# RadioPixelHardware.net
KiCad netlist of a schematic drawn in EAGLE
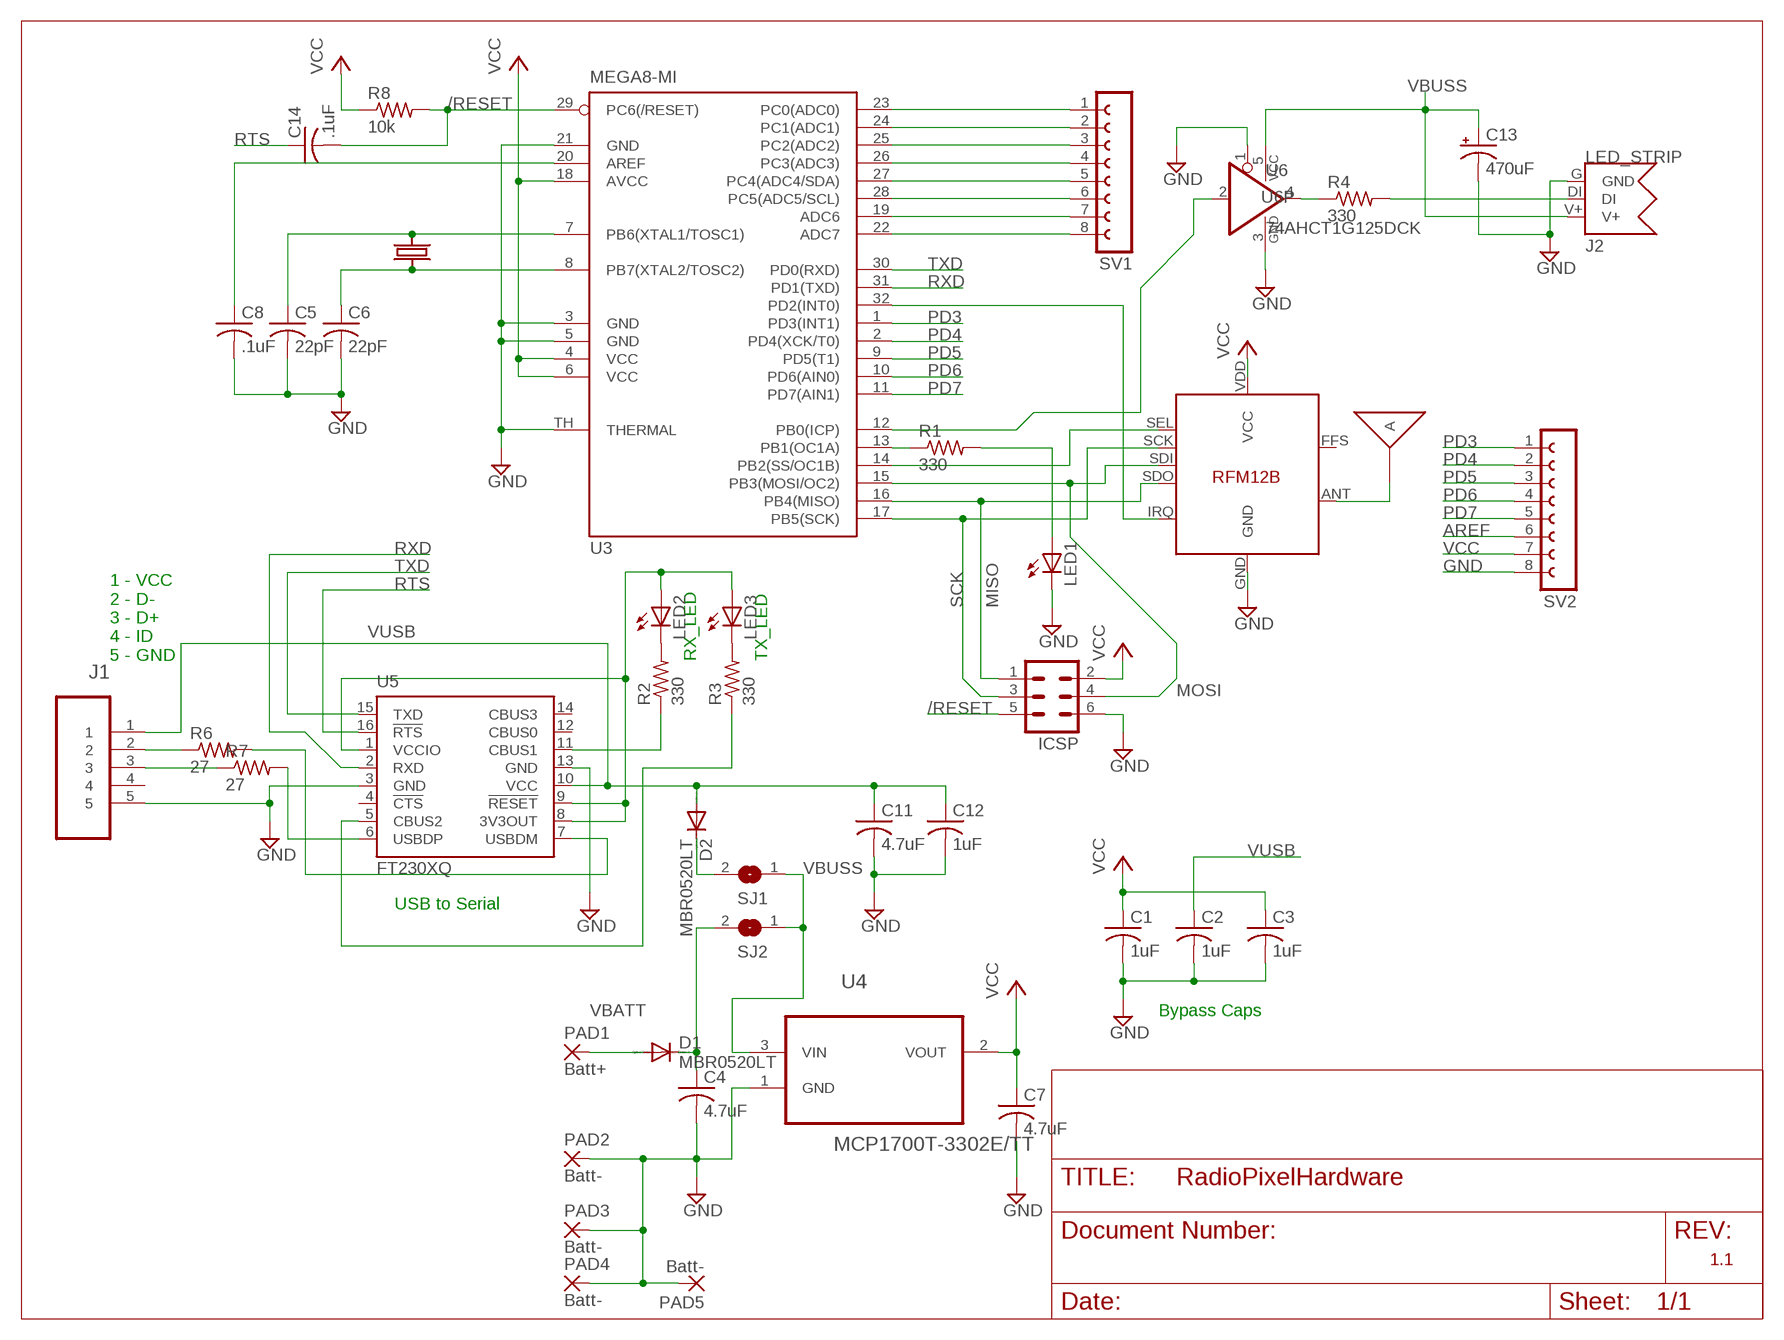
[diagram p0: schematic, sheet 1]

(export (version "E")
  (design (tool "Eeschema 10.0.6"))
  (components
    (comp (ref "C1")
      (value "1uF")
      (footprint "eagle-import:C0603")
      (libsource (lib "eagle-import") (part "C-USC0603"))
    )
    (comp (ref "C2")
      (value "1uF")
      (footprint "eagle-import:C0603")
      (libsource (lib "eagle-import") (part "C-USC0603"))
    )
    (comp (ref "C3")
      (value "1uF")
      (footprint "eagle-import:C0603")
      (libsource (lib "eagle-import") (part "C-USC0603"))
    )
    (comp (ref "C4")
      (value "4.7uF")
      (footprint "eagle-import:C0603")
      (libsource (lib "eagle-import") (part "C-USC0603"))
    )
    (comp (ref "C5")
      (value "22pF")
      (footprint "eagle-import:C0603")
      (libsource (lib "eagle-import") (part "C-USC0603"))
    )
    (comp (ref "C6")
      (value "22pF")
      (footprint "eagle-import:C0603")
      (libsource (lib "eagle-import") (part "C-USC0603"))
    )
    (comp (ref "C7")
      (value "4.7uF")
      (footprint "eagle-import:C0603")
      (libsource (lib "eagle-import") (part "C-USC0603"))
    )
    (comp (ref "C8")
      (value ".1uF")
      (footprint "eagle-import:C0603")
      (libsource (lib "eagle-import") (part "C-USC0603"))
    )
    (comp (ref "C11")
      (value "4.7uF")
      (footprint "eagle-import:C0603")
      (libsource (lib "eagle-import") (part "C-USC0603"))
    )
    (comp (ref "C12")
      (value "1uF")
      (footprint "eagle-import:C0603")
      (libsource (lib "eagle-import") (part "C-USC0603"))
    )
    (comp (ref "C13")
      (value "470uF")
      (footprint "eagle-import:TT2D4L")
      (libsource (lib "eagle-import") (part "CPOL-USTT2D4L"))
    )
    (comp (ref "C14")
      (value ".1uF")
      (footprint "eagle-import:C0603")
      (libsource (lib "eagle-import") (part "C-USC0603"))
    )
    (comp (ref "D1")
      (value "MBR0520LT")
      (footprint "eagle-import:SOD123")
      (libsource (lib "eagle-import") (part "MBR0520LT"))
    )
    (comp (ref "D2")
      (value "MBR0520LT")
      (footprint "eagle-import:SOD123")
      (libsource (lib "eagle-import") (part "MBR0520LT"))
    )
    (comp (ref "ICSP")
      (value "MA03-2")
      (footprint "eagle-import:MA03-2")
      (libsource (lib "eagle-import") (part "MA03-2"))
    )
    (comp (ref "J1")
      (value "47346-0001")
      (footprint "eagle-import:MOLEX_47346-0001")
      (libsource (lib "eagle-import") (part "47346-0001"))
    )
    (comp (ref "J2")
      (value "LED_STRIP")
      (footprint "eagle-import:LEDSTRIP_HEAD")
      (libsource (lib "eagle-import") (part "LED_STRIP"))
    )
    (comp (ref "LED1")
      (value "LEDSML0603")
      (footprint "eagle-import:SML0603")
      (libsource (lib "eagle-import") (part "LEDSML0603"))
    )
    (comp (ref "LED2")
      (value "LEDSML0603")
      (footprint "eagle-import:SML0603")
      (libsource (lib "eagle-import") (part "LEDSML0603"))
    )
    (comp (ref "LED3")
      (value "LEDSML0603")
      (footprint "eagle-import:SML0603")
      (libsource (lib "eagle-import") (part "LEDSML0603"))
    )
    (comp (ref "PAD1")
      (value "Batt+")
      (footprint "eagle-import:1,6_0,8")
      (libsource (lib "eagle-import") (part "1,6/0,8"))
    )
    (comp (ref "PAD2")
      (value "Batt-")
      (footprint "eagle-import:1,6_0,8")
      (libsource (lib "eagle-import") (part "1,6/0,8"))
    )
    (comp (ref "PAD3")
      (value "Batt-")
      (footprint "eagle-import:1,6_0,8")
      (libsource (lib "eagle-import") (part "1,6/0,8"))
    )
    (comp (ref "PAD4")
      (value "Batt-")
      (footprint "eagle-import:1,6_0,8")
      (libsource (lib "eagle-import") (part "1,6/0,8"))
    )
    (comp (ref "PAD5")
      (value "Batt-")
      (footprint "eagle-import:1,6_0,8")
      (libsource (lib "eagle-import") (part "1,6/0,8"))
    )
    (comp (ref "R1")
      (value "330")
      (footprint "eagle-import:R0603")
      (libsource (lib "eagle-import") (part "R-US_R0603"))
    )
    (comp (ref "R2")
      (value "330")
      (footprint "eagle-import:R0603")
      (libsource (lib "eagle-import") (part "R-US_R0603"))
    )
    (comp (ref "R3")
      (value "330")
      (footprint "eagle-import:R0603")
      (libsource (lib "eagle-import") (part "R-US_R0603"))
    )
    (comp (ref "R4")
      (value "330")
      (footprint "eagle-import:R0603")
      (libsource (lib "eagle-import") (part "R-US_R0603"))
    )
    (comp (ref "R6")
      (value "27")
      (footprint "eagle-import:R0603")
      (libsource (lib "eagle-import") (part "R-US_R0603"))
    )
    (comp (ref "R7")
      (value "27")
      (footprint "eagle-import:R0603")
      (libsource (lib "eagle-import") (part "R-US_R0603"))
    )
    (comp (ref "R8")
      (value "10k")
      (footprint "eagle-import:R0603")
      (libsource (lib "eagle-import") (part "R-US_R0603"))
    )
    (comp (ref "SJ1") (value "SJ") (footprint "eagle-import:SJ") (libsource (lib "eagle-import") (part "SJ")))
    (comp (ref "SJ2") (value "SJ") (footprint "eagle-import:SJ") (libsource (lib "eagle-import") (part "SJ")))
    (comp (ref "SV1")
      (value "FE08-1")
      (footprint "eagle-import:FE08")
      (libsource (lib "eagle-import") (part "FE08-1"))
    )
    (comp (ref "SV2")
      (value "FE08-1")
      (footprint "eagle-import:FE08")
      (libsource (lib "eagle-import") (part "FE08-1"))
    )
    (comp (ref "U$2")
      (value "ANTANT-PCB-868MHZ")
      (footprint "eagle-import:ANT-900MHZ-60DBM")
      (libsource (lib "eagle-import") (part "ANTANT-PCB-868MHZ"))
    )
    (comp (ref "U2")
      (value "RFM12B")
      (footprint "eagle-import:RFM12B")
      (libsource (lib "eagle-import") (part "RFM12B"))
    )
    (comp (ref "U3")
      (value "MEGA8-MI")
      (footprint "eagle-import:MLF32-TH")
      (fields (field (name "MPN") "ATMEGA88PA-MU"))
      (libsource (lib "eagle-import") (part "MEGA8-MI"))
    )
    (comp (ref "U4")
      (value "MCP1700T-3302E/TT")
      (footprint "eagle-import:SOT95P237X112-3N")
      (libsource (lib "eagle-import") (part "MCP1700T-3302E/TT"))
    )
    (comp (ref "U5")
      (value "FT230XQ")
      (footprint "eagle-import:QFN16")
      (libsource (lib "eagle-import") (part "FT230XQ"))
    )
    (comp (ref "U6")
      (value "74AHCT1G125DCK")
      (footprint "eagle-import:SC70-5")
      (fields (field (name "OC_NEWARK") "76C1732"))
      (libsource (lib "eagle-import") (part "741G125DCKAHCT"))
    )
    (comp (ref "X1")
      (value "CRYSTAL3.2MMX2.5MM")
      (footprint "eagle-import:XTAL-SMD-3.2X2.5")
      (libsource (lib "eagle-import") (part "CRYSTAL3.2MMX2.5MM"))
    )
  )
  (nets
    (net (code "1") (name "/AREF") (class "Default")
      (node (ref "C8") (pin "1") (pinfunction "1_1") (pintype "passive"))
      (node (ref "SV2") (pin "6") (pinfunction "6_6") (pintype "passive"))
      (node (ref "U3") (pin "20") (pinfunction "AREF_20") (pintype "passive"))
    )
    (net (code "2") (name "/MISO") (class "Default")
      (node (ref "ICSP") (pin "1") (pinfunction "1_1") (pintype "passive"))
      (node (ref "U2") (pin "SDO") (pinfunction "SDO_SDO") (pintype "output"))
      (node (ref "U3") (pin "16") (pinfunction "PB4(MISO)_16") (pintype "bidirectional"))
    )
    (net (code "3") (name "/MOSI") (class "Default")
      (node (ref "ICSP") (pin "4") (pinfunction "4_4") (pintype "passive"))
      (node (ref "U2") (pin "SDI") (pinfunction "SDI_SDI") (pintype "input"))
      (node (ref "U3") (pin "15") (pinfunction "PB3(MOSI/OC2)_15") (pintype "bidirectional"))
    )
    (net (code "4") (name "/PD3") (class "Default")
      (node (ref "SV2") (pin "1") (pinfunction "1_1") (pintype "passive"))
      (node (ref "U3") (pin "1") (pinfunction "PD3(INT1)_1") (pintype "bidirectional"))
    )
    (net (code "5") (name "/PD4") (class "Default")
      (node (ref "SV2") (pin "2") (pinfunction "2_2") (pintype "passive"))
      (node (ref "U3") (pin "2") (pinfunction "PD4(XCK/T0)_2") (pintype "bidirectional"))
    )
    (net (code "6") (name "/PD5") (class "Default")
      (node (ref "SV2") (pin "3") (pinfunction "3_3") (pintype "passive"))
      (node (ref "U3") (pin "9") (pinfunction "PD5(T1)_9") (pintype "bidirectional"))
    )
    (net (code "7") (name "/PD6") (class "Default")
      (node (ref "SV2") (pin "4") (pinfunction "4_4") (pintype "passive"))
      (node (ref "U3") (pin "10") (pinfunction "PD6(AIN0)_10") (pintype "bidirectional"))
    )
    (net (code "8") (name "/PD7") (class "Default")
      (node (ref "SV2") (pin "5") (pinfunction "5_5") (pintype "passive"))
      (node (ref "U3") (pin "11") (pinfunction "PD7(AIN1)_11") (pintype "bidirectional"))
    )
    (net (code "9") (name "/RTS") (class "Default")
      (node (ref "C14") (pin "1") (pinfunction "1_1") (pintype "passive"))
      (node (ref "U5") (pin "16") (pinfunction "~{RTS}_16") (pintype "output"))
    )
    (net (code "10") (name "/RXD") (class "Default")
      (node (ref "U3") (pin "31") (pinfunction "PD1(TXD)_31") (pintype "bidirectional"))
      (node (ref "U5") (pin "2") (pinfunction "RXD_2") (pintype "input"))
    )
    (net (code "11") (name "/SCK") (class "Default")
      (node (ref "ICSP") (pin "3") (pinfunction "3_3") (pintype "passive"))
      (node (ref "U2") (pin "SCK") (pinfunction "SCK_SCK") (pintype "input"))
      (node (ref "U3") (pin "17") (pinfunction "PB5(SCK)_17") (pintype "bidirectional"))
    )
    (net (code "12") (name "/TXD") (class "Default")
      (node (ref "U3") (pin "30") (pinfunction "PD0(RXD)_30") (pintype "bidirectional"))
      (node (ref "U5") (pin "15") (pinfunction "TXD_15") (pintype "output"))
    )
    (net (code "13") (name "/VBATT") (class "Default")
      (node (ref "D1") (pin "A") (pinfunction "A_A") (pintype "passive"))
      (node (ref "PAD1") (pin "1") (pinfunction "P_1") (pintype "passive"))
    )
    (net (code "14") (name "/VBUSS") (class "Default")
      (node (ref "C13") (pin "+") (pinfunction "+_+") (pintype "passive"))
      (node (ref "J2") (pin "V+") (pinfunction "V+_V+") (pintype "bidirectional"))
      (node (ref "SJ1") (pin "1") (pinfunction "1_1") (pintype "passive"))
      (node (ref "SJ2") (pin "1") (pinfunction "1_1") (pintype "passive"))
      (node (ref "U4") (pin "3") (pinfunction "VIN_3") (pintype "input"))
      (node (ref "U6") (pin "5") (pinfunction "VCC_5") (pintype "power_in"))
    )
    (net (code "15") (name "/VUSB") (class "Default")
      (node (ref "C11") (pin "1") (pinfunction "1_1") (pintype "passive"))
      (node (ref "C12") (pin "1") (pinfunction "1_1") (pintype "passive"))
      (node (ref "C2") (pin "1") (pinfunction "1_1") (pintype "passive"))
      (node (ref "D2") (pin "A") (pinfunction "A_A") (pintype "passive"))
      (node (ref "J1") (pin "1") (pinfunction "1_1") (pintype "input"))
      (node (ref "U5") (pin "10") (pinfunction "VCC_10") (pintype "power_in"))
    )
    (net (code "16") (name "/{slash}RESET") (class "Default")
      (node (ref "C14") (pin "2") (pinfunction "2_2") (pintype "passive"))
      (node (ref "ICSP") (pin "5") (pinfunction "5_5") (pintype "passive"))
      (node (ref "R8") (pin "2") (pinfunction "2_2") (pintype "passive"))
      (node (ref "U3") (pin "29") (pinfunction "PC6(/RESET)_29") (pintype "bidirectional"))
    )
    (net (code "17") (name "GND") (class "Default")
      (node (ref "C1") (pin "2") (pinfunction "2_2") (pintype "passive"))
      (node (ref "C11") (pin "2") (pinfunction "2_2") (pintype "passive"))
      (node (ref "C12") (pin "2") (pinfunction "2_2") (pintype "passive"))
      (node (ref "C13") (pin "-") (pinfunction "-_-") (pintype "passive"))
      (node (ref "C2") (pin "2") (pinfunction "2_2") (pintype "passive"))
      (node (ref "C3") (pin "2") (pinfunction "2_2") (pintype "passive"))
      (node (ref "C4") (pin "2") (pinfunction "2_2") (pintype "passive"))
      (node (ref "C5") (pin "2") (pinfunction "2_2") (pintype "passive"))
      (node (ref "C6") (pin "2") (pinfunction "2_2") (pintype "passive"))
      (node (ref "C7") (pin "2") (pinfunction "2_2") (pintype "passive"))
      (node (ref "C8") (pin "2") (pinfunction "2_2") (pintype "passive"))
      (node (ref "ICSP") (pin "6") (pinfunction "6_6") (pintype "passive"))
      (node (ref "J1") (pin "5") (pinfunction "5_5") (pintype "input"))
      (node (ref "J2") (pin "G") (pinfunction "GND_G") (pintype "bidirectional"))
      (node (ref "LED1") (pin "C") (pinfunction "C_C") (pintype "passive"))
      (node (ref "PAD2") (pin "1") (pinfunction "P_1") (pintype "passive"))
      (node (ref "PAD3") (pin "1") (pinfunction "P_1") (pintype "passive"))
      (node (ref "PAD4") (pin "1") (pinfunction "P_1") (pintype "passive"))
      (node (ref "PAD5") (pin "1") (pinfunction "P_1") (pintype "passive"))
      (node (ref "SV2") (pin "8") (pinfunction "8_8") (pintype "passive"))
      (node (ref "U2") (pin "GND") (pinfunction "GND_GND") (pintype "power_in"))
      (node (ref "U3") (pin "21") (pinfunction "GND_21") (pintype "power_in"))
      (node (ref "U3") (pin "3") (pinfunction "GND_3") (pintype "power_in"))
      (node (ref "U3") (pin "5") (pinfunction "GND_5") (pintype "power_in"))
      (node (ref "U3") (pin "TH") (pinfunction "THERMAL_TH") (pintype "passive"))
      (node (ref "U4") (pin "1") (pinfunction "GND_1") (pintype "passive"))
      (node (ref "U5") (pin "13") (pinfunction "GND_13") (pintype "power_in"))
      (node (ref "U5") (pin "3") (pinfunction "GND_3") (pintype "power_in"))
      (node (ref "U6") (pin "1") (pinfunction "OE_1") (pintype "input"))
      (node (ref "U6") (pin "3") (pinfunction "GND_3") (pintype "power_in"))
    )
    (net (code "18") (name "Net-(C4-Pad1)") (class "Default")
      (node (ref "C4") (pin "1") (pinfunction "1_1") (pintype "passive"))
      (node (ref "D1") (pin "C") (pinfunction "C_C") (pintype "passive"))
      (node (ref "SJ2") (pin "2") (pinfunction "2_2") (pintype "passive"))
    )
    (net (code "19") (name "Net-(D2-PadC)") (class "Default")
      (node (ref "D2") (pin "C") (pinfunction "C_C") (pintype "passive"))
      (node (ref "SJ1") (pin "2") (pinfunction "2_2") (pintype "passive"))
    )
    (net (code "20") (name "Net-(J1-Pad2)") (class "Default")
      (node (ref "J1") (pin "2") (pinfunction "2_2") (pintype "input"))
      (node (ref "R6") (pin "1") (pinfunction "1_1") (pintype "passive"))
    )
    (net (code "21") (name "Net-(J1-Pad3)") (class "Default")
      (node (ref "J1") (pin "3") (pinfunction "3_3") (pintype "input"))
      (node (ref "R7") (pin "1") (pinfunction "1_1") (pintype "passive"))
    )
    (net (code "22") (name "Net-(J2-PadDI)") (class "Default")
      (node (ref "J2") (pin "DI") (pinfunction "DI_DI") (pintype "bidirectional"))
      (node (ref "R4") (pin "2") (pinfunction "2_2") (pintype "passive"))
    )
    (net (code "23") (name "Net-(LED1-PadA)") (class "Default")
      (node (ref "LED1") (pin "A") (pinfunction "A_A") (pintype "passive"))
      (node (ref "R1") (pin "2") (pinfunction "2_2") (pintype "passive"))
    )
    (net (code "24") (name "Net-(LED2-PadC)") (class "Default")
      (node (ref "LED2") (pin "C") (pinfunction "C_C") (pintype "passive"))
      (node (ref "R2") (pin "2") (pinfunction "2_2") (pintype "passive"))
    )
    (net (code "25") (name "Net-(LED3-PadC)") (class "Default")
      (node (ref "LED3") (pin "C") (pinfunction "C_C") (pintype "passive"))
      (node (ref "R3") (pin "2") (pinfunction "2_2") (pintype "passive"))
    )
    (net (code "26") (name "Net-(U$2-A)") (class "Default")
      (node (ref "U$2") (pin "P$1") (pinfunction "A_P$1") (pintype "passive"))
      (node (ref "U2") (pin "ANT") (pinfunction "ANT_ANT") (pintype "passive"))
    )
    (net (code "27") (name "Net-(U3-ADC6)") (class "Default")
      (node (ref "SV1") (pin "7") (pinfunction "7_7") (pintype "passive"))
      (node (ref "U3") (pin "19") (pinfunction "ADC6_19") (pintype "bidirectional"))
    )
    (net (code "28") (name "Net-(U3-ADC7)") (class "Default")
      (node (ref "SV1") (pin "8") (pinfunction "8_8") (pintype "passive"))
      (node (ref "U3") (pin "22") (pinfunction "ADC7_22") (pintype "bidirectional"))
    )
    (net (code "29") (name "Net-(U3-PB0(ICP))") (class "Default")
      (node (ref "U3") (pin "12") (pinfunction "PB0(ICP)_12") (pintype "bidirectional"))
      (node (ref "U6") (pin "2") (pinfunction "I_2") (pintype "input"))
    )
    (net (code "30") (name "Net-(U3-PB1(OC1A))") (class "Default")
      (node (ref "R1") (pin "1") (pinfunction "1_1") (pintype "passive"))
      (node (ref "U3") (pin "13") (pinfunction "PB1(OC1A)_13") (pintype "bidirectional"))
    )
    (net (code "31") (name "Net-(U3-PB2(SS{slash}OC1B))") (class "Default")
      (node (ref "U2") (pin "SEL") (pinfunction "SEL_SEL") (pintype "input"))
      (node (ref "U3") (pin "14") (pinfunction "PB2(SS/OC1B)_14") (pintype "bidirectional"))
    )
    (net (code "32") (name "Net-(U3-PB6(XTAL1{slash}TOSC1))") (class "Default")
      (node (ref "C5") (pin "1") (pinfunction "1_1") (pintype "passive"))
      (node (ref "U3") (pin "7") (pinfunction "PB6(XTAL1/TOSC1)_7") (pintype "bidirectional"))
      (node (ref "X1") (pin "3") (pinfunction "2_3") (pintype "passive"))
    )
    (net (code "33") (name "Net-(U3-PB7(XTAL2{slash}TOSC2))") (class "Default")
      (node (ref "C6") (pin "1") (pinfunction "1_1") (pintype "passive"))
      (node (ref "U3") (pin "8") (pinfunction "PB7(XTAL2/TOSC2)_8") (pintype "bidirectional"))
      (node (ref "X1") (pin "1") (pinfunction "1_1") (pintype "bidirectional"))
    )
    (net (code "34") (name "Net-(U3-PC0(ADC0))") (class "Default")
      (node (ref "SV1") (pin "1") (pinfunction "1_1") (pintype "passive"))
      (node (ref "U3") (pin "23") (pinfunction "PC0(ADC0)_23") (pintype "bidirectional"))
    )
    (net (code "35") (name "Net-(U3-PC1(ADC1))") (class "Default")
      (node (ref "SV1") (pin "2") (pinfunction "2_2") (pintype "passive"))
      (node (ref "U3") (pin "24") (pinfunction "PC1(ADC1)_24") (pintype "bidirectional"))
    )
    (net (code "36") (name "Net-(U3-PC2(ADC2))") (class "Default")
      (node (ref "SV1") (pin "3") (pinfunction "3_3") (pintype "passive"))
      (node (ref "U3") (pin "25") (pinfunction "PC2(ADC2)_25") (pintype "bidirectional"))
    )
    (net (code "37") (name "Net-(U3-PC3(ADC3))") (class "Default")
      (node (ref "SV1") (pin "4") (pinfunction "4_4") (pintype "passive"))
      (node (ref "U3") (pin "26") (pinfunction "PC3(ADC3)_26") (pintype "bidirectional"))
    )
    (net (code "38") (name "Net-(U3-PC4(ADC4{slash}SDA))") (class "Default")
      (node (ref "SV1") (pin "5") (pinfunction "5_5") (pintype "passive"))
      (node (ref "U3") (pin "27") (pinfunction "PC4(ADC4/SDA)_27") (pintype "bidirectional"))
    )
    (net (code "39") (name "Net-(U3-PC5(ADC5{slash}SCL))") (class "Default")
      (node (ref "SV1") (pin "6") (pinfunction "6_6") (pintype "passive"))
      (node (ref "U3") (pin "28") (pinfunction "PC5(ADC5/SCL)_28") (pintype "bidirectional"))
    )
    (net (code "40") (name "Net-(U3-PD2(INT0))") (class "Default")
      (node (ref "U2") (pin "IRQ") (pinfunction "IRQ_IRQ") (pintype "open_collector"))
      (node (ref "U3") (pin "32") (pinfunction "PD2(INT0)_32") (pintype "bidirectional"))
    )
    (net (code "41") (name "Net-(U5-3V3OUT)") (class "Default")
      (node (ref "LED2") (pin "A") (pinfunction "A_A") (pintype "passive"))
      (node (ref "LED3") (pin "A") (pinfunction "A_A") (pintype "passive"))
      (node (ref "U5") (pin "1") (pinfunction "VCCIO_1") (pintype "power_in"))
      (node (ref "U5") (pin "8") (pinfunction "3V3OUT_8") (pintype "output"))
      (node (ref "U5") (pin "9") (pinfunction "~{RESET}_9") (pintype "input"))
    )
    (net (code "42") (name "Net-(U5-CBUS1)") (class "Default")
      (node (ref "R2") (pin "1") (pinfunction "1_1") (pintype "passive"))
      (node (ref "U5") (pin "11") (pinfunction "CBUS1_11") (pintype "bidirectional"))
    )
    (net (code "43") (name "Net-(U5-CBUS2)") (class "Default")
      (node (ref "R3") (pin "1") (pinfunction "1_1") (pintype "passive"))
      (node (ref "U5") (pin "5") (pinfunction "CBUS2_5") (pintype "bidirectional"))
    )
    (net (code "44") (name "Net-(U5-USBDM)") (class "Default")
      (node (ref "R6") (pin "2") (pinfunction "2_2") (pintype "passive"))
      (node (ref "U5") (pin "7") (pinfunction "USBDM_7") (pintype "input"))
    )
    (net (code "45") (name "Net-(U5-USBDP)") (class "Default")
      (node (ref "R7") (pin "2") (pinfunction "2_2") (pintype "passive"))
      (node (ref "U5") (pin "6") (pinfunction "USBDP_6") (pintype "input"))
    )
    (net (code "46") (name "Net-(U6A-O)") (class "Default")
      (node (ref "R4") (pin "1") (pinfunction "1_1") (pintype "passive"))
      (node (ref "U6") (pin "4") (pinfunction "O_4") (pintype "tri_state"))
    )
    (net (code "47") (name "VCC") (class "Default")
      (node (ref "C1") (pin "1") (pinfunction "1_1") (pintype "passive"))
      (node (ref "C3") (pin "1") (pinfunction "1_1") (pintype "passive"))
      (node (ref "C7") (pin "1") (pinfunction "1_1") (pintype "passive"))
      (node (ref "ICSP") (pin "2") (pinfunction "2_2") (pintype "passive"))
      (node (ref "R8") (pin "1") (pinfunction "1_1") (pintype "passive"))
      (node (ref "SV2") (pin "7") (pinfunction "7_7") (pintype "passive"))
      (node (ref "U2") (pin "VDD") (pinfunction "VCC_VDD") (pintype "power_in"))
      (node (ref "U3") (pin "18") (pinfunction "AVCC_18") (pintype "power_in"))
      (node (ref "U3") (pin "4") (pinfunction "VCC_4") (pintype "power_in"))
      (node (ref "U3") (pin "6") (pinfunction "VCC_6") (pintype "power_in"))
      (node (ref "U4") (pin "2") (pinfunction "VOUT_2") (pintype "output"))
    )
    (net (code "48") (name "unconnected-(J1-Pad4)") (class "Default")
      (node (ref "J1") (pin "4") (pinfunction "4_4") (pintype "input"))
    )
    (net (code "49") (name "unconnected-(U2-PadFFS)") (class "Default")
      (node (ref "U2") (pin "FFS") (pinfunction "FFS_FFS") (pintype "bidirectional"))
    )
    (net (code "50") (name "unconnected-(U5-CBUS0-Pad12)") (class "Default")
      (node (ref "U5") (pin "12") (pinfunction "CBUS0_12") (pintype "bidirectional"))
    )
    (net (code "51") (name "unconnected-(U5-CBUS3-Pad14)") (class "Default")
      (node (ref "U5") (pin "14") (pinfunction "CBUS3_14") (pintype "bidirectional"))
    )
    (net (code "52") (name "unconnected-(U5-~{CTS}-Pad4)") (class "Default")
      (node (ref "U5") (pin "4") (pinfunction "~{CTS}_4") (pintype "input"))
    )
  )
)
